# SP-3000PCB03.net
KiCad netlist of a schematic drawn in Altium Designer
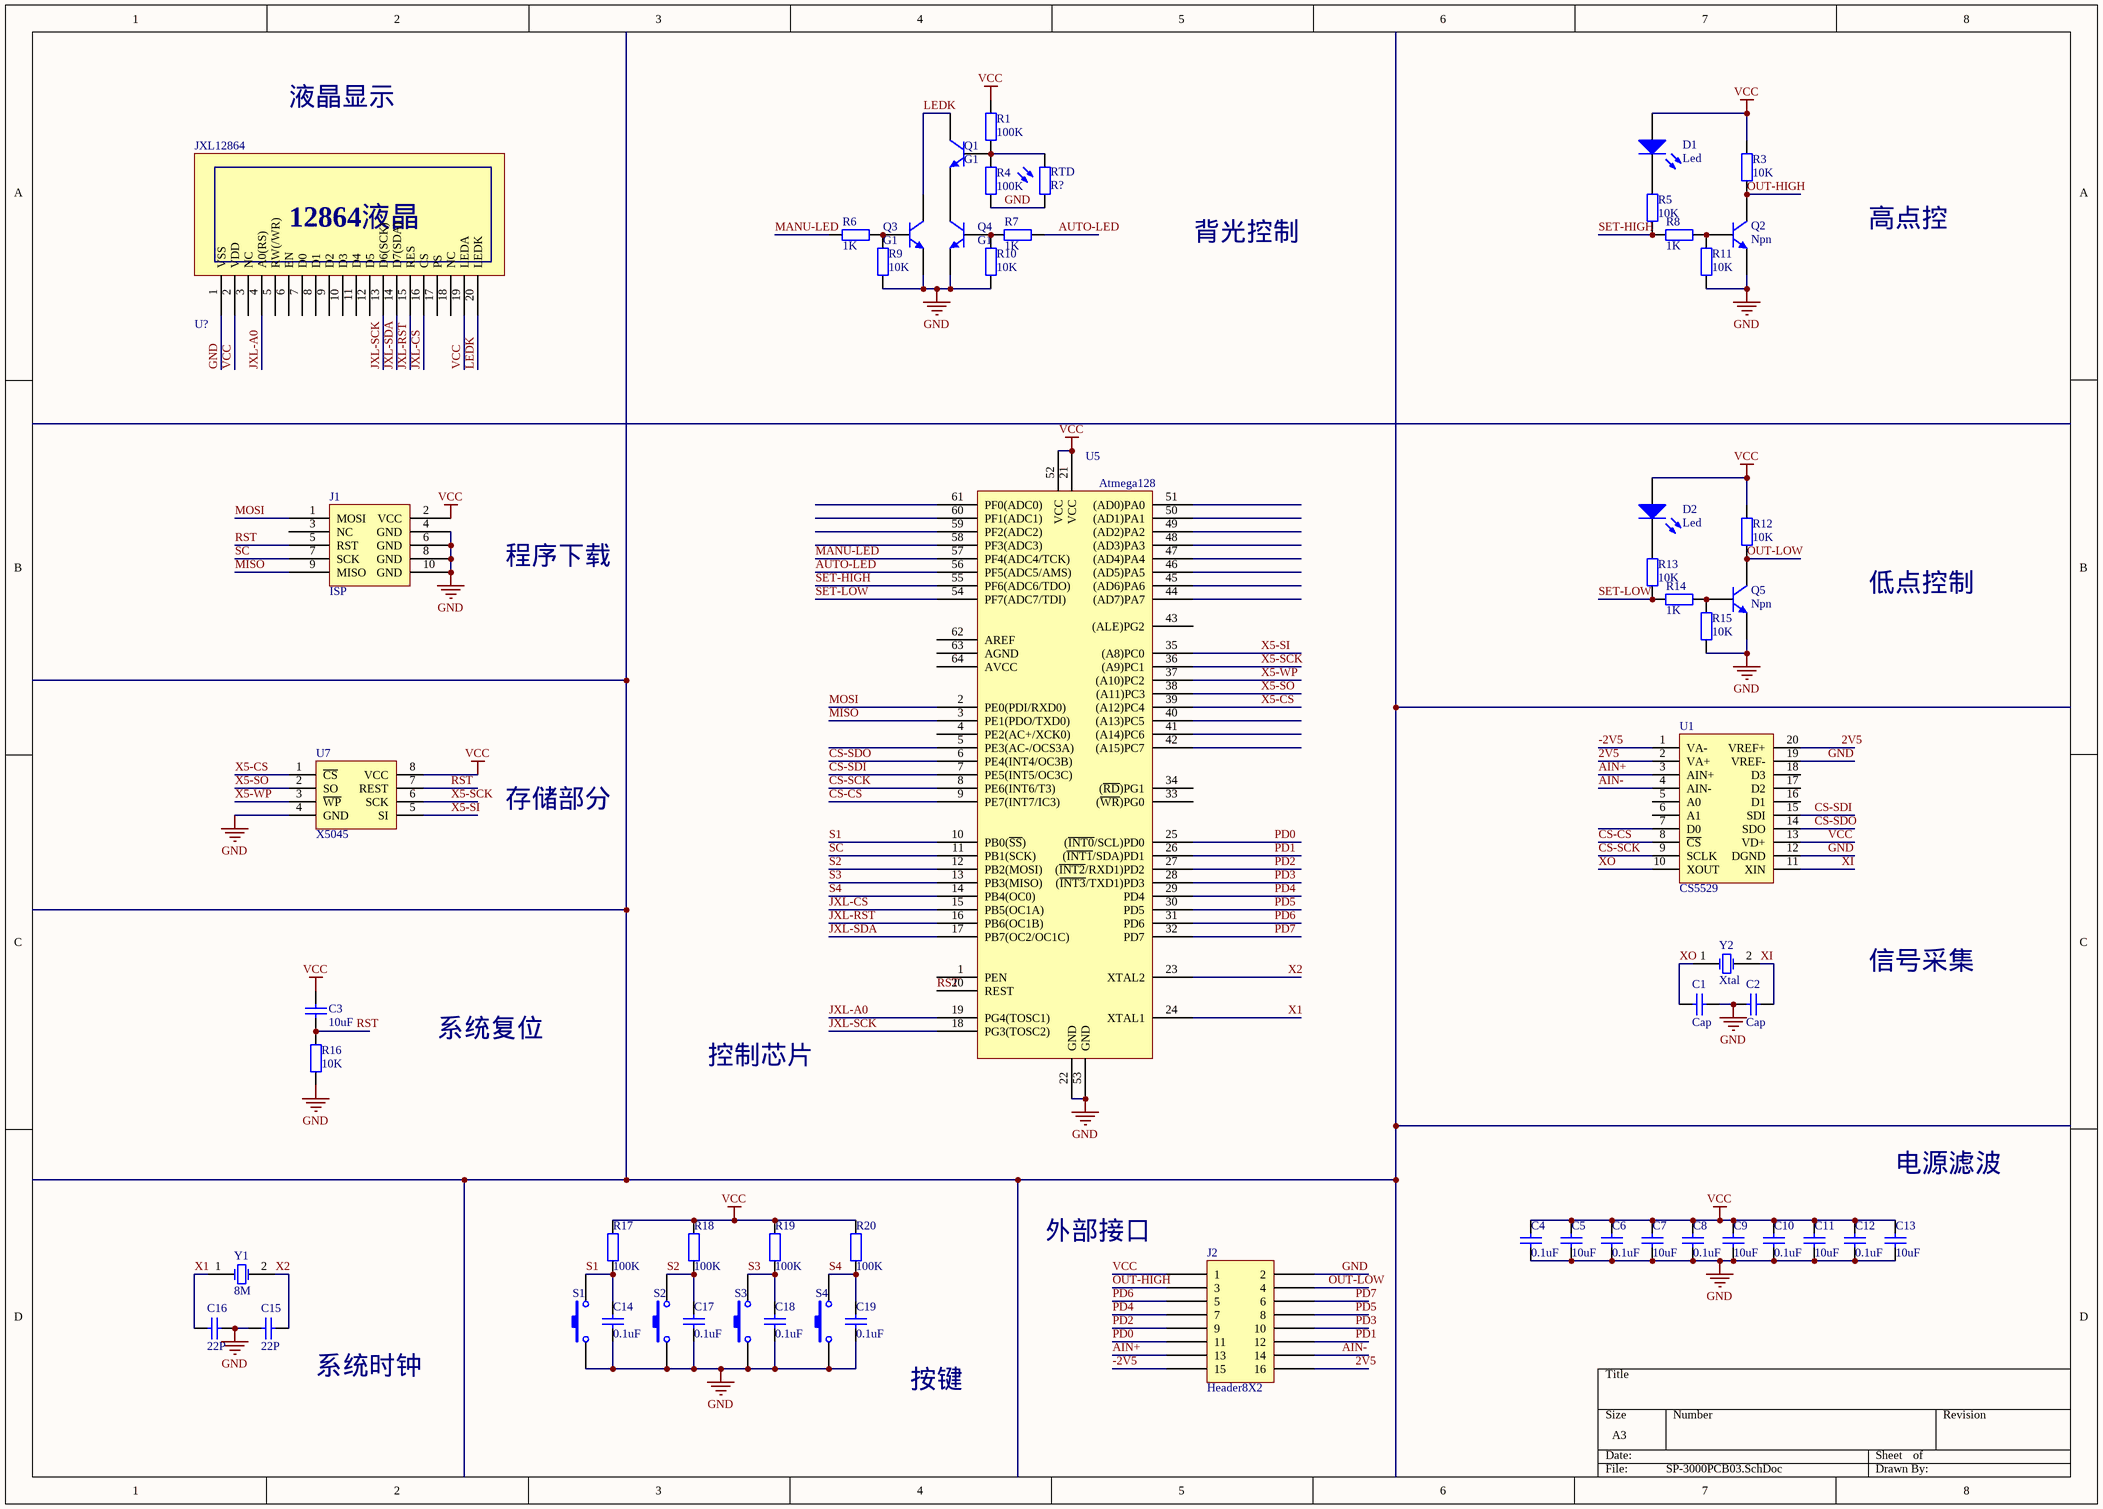
[diagram p0: SP-3000PCB03.SchDoc]

(export (version "E")
  (design (tool "Eeschema 10.0.6"))
  (components
    (comp (ref "C1") (value "Cap") (footprint "0805") (description "C?") (libsource (lib "常用库") (part "Cap")))
    (comp (ref "C2") (value "Cap") (footprint "0805") (description "C?") (libsource (lib "常用库") (part "Cap")))
    (comp (ref "C3")
      (value "10uF")
      (footprint "0805")
      (description "C?")
      (libsource (lib "常用库") (part "Cap"))
    )
    (comp (ref "C4")
      (value "0.1uF")
      (footprint "0805")
      (description "C?")
      (libsource (lib "常用库") (part "Cap"))
    )
    (comp (ref "C5")
      (value "10uF")
      (footprint "0805")
      (description "C?")
      (libsource (lib "常用库") (part "Cap"))
    )
    (comp (ref "C6")
      (value "0.1uF")
      (footprint "0805")
      (description "C?")
      (libsource (lib "常用库") (part "Cap"))
    )
    (comp (ref "C7")
      (value "10uF")
      (footprint "0805")
      (description "C?")
      (libsource (lib "常用库") (part "Cap"))
    )
    (comp (ref "C8")
      (value "0.1uF")
      (footprint "0805")
      (description "C?")
      (libsource (lib "常用库") (part "Cap"))
    )
    (comp (ref "C9")
      (value "10uF")
      (footprint "0805")
      (description "C?")
      (libsource (lib "常用库") (part "Cap"))
    )
    (comp (ref "C10")
      (value "0.1uF")
      (footprint "0805")
      (description "C?")
      (libsource (lib "常用库") (part "Cap"))
    )
    (comp (ref "C11")
      (value "10uF")
      (footprint "0805")
      (description "C?")
      (libsource (lib "常用库") (part "Cap"))
    )
    (comp (ref "C12")
      (value "0.1uF")
      (footprint "0805")
      (description "C?")
      (libsource (lib "常用库") (part "Cap"))
    )
    (comp (ref "C13")
      (value "10uF")
      (footprint "0805")
      (description "C?")
      (libsource (lib "常用库") (part "Cap"))
    )
    (comp (ref "C14")
      (value "0.1uF")
      (footprint "0805")
      (description "C?")
      (libsource (lib "常用库") (part "Cap"))
    )
    (comp (ref "C15")
      (value "22P")
      (footprint "0805")
      (description "C?")
      (libsource (lib "常用库") (part "Cap"))
    )
    (comp (ref "C16")
      (value "22P")
      (footprint "0805")
      (description "C?")
      (libsource (lib "常用库") (part "Cap"))
    )
    (comp (ref "C17")
      (value "0.1uF")
      (footprint "0805")
      (description "C?")
      (libsource (lib "常用库") (part "Cap"))
    )
    (comp (ref "C18")
      (value "0.1uF")
      (footprint "0805")
      (description "C?")
      (libsource (lib "常用库") (part "Cap"))
    )
    (comp (ref "C19")
      (value "0.1uF")
      (footprint "0805")
      (description "C?")
      (libsource (lib "常用库") (part "Cap"))
    )
    (comp (ref "D1") (value "Led") (footprint "LED") (description "D?") (libsource (lib "常用库") (part "Led")))
    (comp (ref "D2") (value "Led") (footprint "LED") (description "D?") (libsource (lib "常用库") (part "Led")))
    (comp (ref "J1")
      (value "ISP")
      (footprint "IDC10")
      (description "U?")
      (libsource (lib "常用库") (part "isp"))
    )
    (comp (ref "J2")
      (value "Header8X2")
      (footprint "IDC16")
      (description "H?")
      (libsource (lib "常用库") (part "Header8X2"))
    )
    (comp (ref "JXL12864") (value "U?") (footprint "JLX12864") (libsource (lib "常用库") (part "JLX12864")))
    (comp (ref "Q1") (value "G1") (footprint "9013") (description "Q?") (libsource (lib "常用库") (part "Npn")))
    (comp (ref "Q2") (value "Npn") (footprint "9013") (description "Q?") (libsource (lib "常用库") (part "Npn")))
    (comp (ref "Q3") (value "G1") (footprint "9013") (description "Q?") (libsource (lib "常用库") (part "Npn")))
    (comp (ref "Q4") (value "G1") (footprint "9013") (description "Q?") (libsource (lib "常用库") (part "Npn")))
    (comp (ref "Q5") (value "Npn") (footprint "9013") (description "Q?") (libsource (lib "常用库") (part "Npn")))
    (comp (ref "R1") (value "100K") (footprint "0805") (description "R?") (libsource (lib "") (part "Res_1")))
    (comp (ref "R3") (value "10K") (footprint "0805") (description "R?") (libsource (lib "常用库") (part "Res")))
    (comp (ref "R4") (value "100K") (footprint "0805") (description "R?") (libsource (lib "") (part "Res_1")))
    (comp (ref "R5") (value "10K") (footprint "0805") (description "R?") (libsource (lib "常用库") (part "Res")))
    (comp (ref "R6") (value "1K") (footprint "0805") (description "R?") (libsource (lib "") (part "Res_3")))
    (comp (ref "R7") (value "1K") (footprint "0805") (description "R?") (libsource (lib "") (part "Res_3")))
    (comp (ref "R8") (value "1K") (footprint "0805") (description "R?") (libsource (lib "") (part "Res_2")))
    (comp (ref "R9") (value "10K") (footprint "0805") (description "R?") (libsource (lib "常用库") (part "Res")))
    (comp (ref "R10")
      (value "10K")
      (footprint "0805")
      (description "R?")
      (libsource (lib "常用库") (part "Res"))
    )
    (comp (ref "R11")
      (value "10K")
      (footprint "0805")
      (description "R?")
      (libsource (lib "常用库") (part "Res"))
    )
    (comp (ref "R12")
      (value "10K")
      (footprint "0805")
      (description "R?")
      (libsource (lib "常用库") (part "Res"))
    )
    (comp (ref "R13")
      (value "10K")
      (footprint "0805")
      (description "R?")
      (libsource (lib "常用库") (part "Res"))
    )
    (comp (ref "R14") (value "1K") (footprint "0805") (description "R?") (libsource (lib "") (part "Res_2")))
    (comp (ref "R15")
      (value "10K")
      (footprint "0805")
      (description "R?")
      (libsource (lib "常用库") (part "Res"))
    )
    (comp (ref "R16")
      (value "10K")
      (footprint "0805")
      (description "R?")
      (libsource (lib "常用库") (part "Res"))
    )
    (comp (ref "R17")
      (value "100K")
      (footprint "0805")
      (description "R?")
      (libsource (lib "常用库") (part "Res"))
    )
    (comp (ref "R18")
      (value "100K")
      (footprint "0805")
      (description "R?")
      (libsource (lib "常用库") (part "Res"))
    )
    (comp (ref "R19")
      (value "100K")
      (footprint "0805")
      (description "R?")
      (libsource (lib "常用库") (part "Res"))
    )
    (comp (ref "R20")
      (value "100K")
      (footprint "0805")
      (description "R?")
      (libsource (lib "常用库") (part "Res"))
    )
    (comp (ref "RTD") (value "R?") (footprint "RTD") (libsource (lib "常用库") (part "光敏电阻")))
    (comp (ref "S1") (value "~") (footprint "SW") (description "S?") (libsource (lib "常用库") (part "Sw-pb")))
    (comp (ref "S2") (value "~") (footprint "SW") (description "S?") (libsource (lib "常用库") (part "Sw-pb")))
    (comp (ref "S3") (value "~") (footprint "SW") (description "S?") (libsource (lib "常用库") (part "Sw-pb")))
    (comp (ref "S4") (value "~") (footprint "SW") (description "S?") (libsource (lib "常用库") (part "Sw-pb")))
    (comp (ref "U1") (value "CS5529") (footprint "CS5529") (libsource (lib "常用库") (part "CS5529")))
    (comp (ref "U5")
      (value "Atmega128")
      (footprint "Quad64")
      (description "U?")
      (libsource (lib "常用库") (part "Atmega128"))
    )
    (comp (ref "U7") (value "X5045") (footprint "SOP8") (libsource (lib "常用库") (part "X5045")))
    (comp (ref "Y1") (value "8M") (footprint "CY") (description "Y?") (libsource (lib "常用库") (part "Xtal")))
    (comp (ref "Y2")
      (value "Xtal")
      (footprint "DIP2(32.768M)")
      (description "Y?")
      (libsource (lib "常用库") (part "Xtal"))
    )
  )
  (nets
    (net (code "1") (name "/-2V5") (class "Default")
      (node (ref "J2") (pin "15") (pinfunction "15_15") (pintype "passive"))
      (node (ref "U1") (pin "1") (pinfunction "VA-_1") (pintype "passive"))
    )
    (net (code "2") (name "/2V5") (class "Default")
      (node (ref "J2") (pin "16") (pinfunction "16_16") (pintype "passive"))
      (node (ref "U1") (pin "2") (pinfunction "VA+_2") (pintype "passive"))
      (node (ref "U1") (pin "20") (pinfunction "VREF+_20") (pintype "passive"))
    )
    (net (code "3") (name "/AIN+") (class "Default")
      (node (ref "J2") (pin "13") (pinfunction "13_13") (pintype "passive"))
      (node (ref "U1") (pin "3") (pinfunction "AIN+_3") (pintype "passive"))
    )
    (net (code "4") (name "/AIN-") (class "Default")
      (node (ref "J2") (pin "14") (pinfunction "14_14") (pintype "passive"))
      (node (ref "U1") (pin "4") (pinfunction "AIN-_4") (pintype "passive"))
    )
    (net (code "5") (name "/AUTO-LED") (class "Default")
      (node (ref "R7") (pin "1") (pinfunction "1_1") (pintype "passive"))
      (node (ref "U5") (pin "56") (pinfunction "PF5(ADC5/AMS)_56") (pintype "passive"))
    )
    (net (code "6") (name "/CS-CS") (class "Default")
      (node (ref "U1") (pin "8") (pinfunction "~{CS}_8") (pintype "passive"))
      (node (ref "U5") (pin "9") (pinfunction "PE7(INT7/IC3)_9") (pintype "passive"))
    )
    (net (code "7") (name "/CS-SCK") (class "Default")
      (node (ref "U1") (pin "9") (pinfunction "SCLK_9") (pintype "passive"))
      (node (ref "U5") (pin "8") (pinfunction "PE6(INT6/T3)_8") (pintype "passive"))
    )
    (net (code "8") (name "/CS-SDI") (class "Default")
      (node (ref "U1") (pin "15") (pinfunction "SDI_15") (pintype "passive"))
      (node (ref "U5") (pin "7") (pinfunction "PE5(INT5/OC3C)_7") (pintype "passive"))
    )
    (net (code "9") (name "/CS-SDO") (class "Default")
      (node (ref "U1") (pin "14") (pinfunction "SDO_14") (pintype "passive"))
      (node (ref "U5") (pin "6") (pinfunction "PE4(INT4/OC3B)_6") (pintype "passive"))
    )
    (net (code "10") (name "/JXL-A0") (class "Default")
      (node (ref "JXL12864") (pin "4") (pinfunction "A0(RS)_4") (pintype "passive"))
      (node (ref "U5") (pin "19") (pinfunction "PG4(TOSC1)_19") (pintype "passive"))
    )
    (net (code "11") (name "/JXL-CS") (class "Default")
      (node (ref "JXL12864") (pin "16") (pinfunction "CS_16") (pintype "passive"))
      (node (ref "U5") (pin "15") (pinfunction "PB5(OC1A)_15") (pintype "passive"))
    )
    (net (code "12") (name "/JXL-RST") (class "Default")
      (node (ref "JXL12864") (pin "15") (pinfunction "RES_15") (pintype "passive"))
      (node (ref "U5") (pin "16") (pinfunction "PB6(OC1B)_16") (pintype "passive"))
    )
    (net (code "13") (name "/JXL-SCK") (class "Default")
      (node (ref "JXL12864") (pin "13") (pinfunction "D6(SCK)_13") (pintype "passive"))
      (node (ref "U5") (pin "18") (pinfunction "PG3(TOSC2)_18") (pintype "passive"))
    )
    (net (code "14") (name "/JXL-SDA") (class "Default")
      (node (ref "JXL12864") (pin "14") (pinfunction "D7(SDA)_14") (pintype "passive"))
      (node (ref "U5") (pin "17") (pinfunction "PB7(OC2/OC1C)_17") (pintype "passive"))
    )
    (net (code "15") (name "/LEDK") (class "Default")
      (node (ref "JXL12864") (pin "20") (pinfunction "LEDK_20") (pintype "passive"))
      (node (ref "Q1") (pin "3") (pinfunction "C_3") (pintype "passive"))
      (node (ref "Q3") (pin "3") (pinfunction "C_3") (pintype "passive"))
    )
    (net (code "16") (name "/MANU-LED") (class "Default")
      (node (ref "R6") (pin "2") (pinfunction "2_2") (pintype "passive"))
      (node (ref "U5") (pin "57") (pinfunction "PF4(ADC4/TCK)_57") (pintype "passive"))
    )
    (net (code "17") (name "/MISO") (class "Default")
      (node (ref "J1") (pin "9") (pinfunction "MISO_9") (pintype "passive"))
      (node (ref "U5") (pin "3") (pinfunction "PE1(PDO/TXD0)_3") (pintype "passive"))
    )
    (net (code "18") (name "/MOSI") (class "Default")
      (node (ref "J1") (pin "1") (pinfunction "MOSI_1") (pintype "passive"))
      (node (ref "U5") (pin "2") (pinfunction "PE0(PDI/RXD0)_2") (pintype "passive"))
    )
    (net (code "19") (name "/OUT-HIGH") (class "Default")
      (node (ref "J2") (pin "3") (pinfunction "3_3") (pintype "passive"))
      (node (ref "Q2") (pin "3") (pinfunction "C_3") (pintype "passive"))
      (node (ref "R3") (pin "1") (pinfunction "1_1") (pintype "passive"))
    )
    (net (code "20") (name "/OUT-LOW") (class "Default")
      (node (ref "J2") (pin "4") (pinfunction "4_4") (pintype "passive"))
      (node (ref "Q5") (pin "3") (pinfunction "C_3") (pintype "passive"))
      (node (ref "R12") (pin "1") (pinfunction "1_1") (pintype "passive"))
    )
    (net (code "21") (name "/PD0") (class "Default")
      (node (ref "J2") (pin "11") (pinfunction "11_11") (pintype "passive"))
      (node (ref "U5") (pin "25") (pinfunction "(~{INT0}/SCL)PD0_25") (pintype "passive"))
    )
    (net (code "22") (name "/PD1") (class "Default")
      (node (ref "J2") (pin "12") (pinfunction "12_12") (pintype "passive"))
      (node (ref "U5") (pin "26") (pinfunction "(~{INT1}/SDA)PD1_26") (pintype "passive"))
    )
    (net (code "23") (name "/PD2") (class "Default")
      (node (ref "J2") (pin "9") (pinfunction "9_9") (pintype "passive"))
      (node (ref "U5") (pin "27") (pinfunction "(~{INT2}/RXD1)PD2_27") (pintype "passive"))
    )
    (net (code "24") (name "/PD3") (class "Default")
      (node (ref "J2") (pin "10") (pinfunction "10_10") (pintype "passive"))
      (node (ref "U5") (pin "28") (pinfunction "(~{INT3}/TXD1)PD3_28") (pintype "passive"))
    )
    (net (code "25") (name "/PD4") (class "Default")
      (node (ref "J2") (pin "7") (pinfunction "7_7") (pintype "passive"))
      (node (ref "U5") (pin "29") (pinfunction "PD4_29") (pintype "passive"))
    )
    (net (code "26") (name "/PD5") (class "Default")
      (node (ref "J2") (pin "8") (pinfunction "8_8") (pintype "passive"))
      (node (ref "U5") (pin "30") (pinfunction "PD5_30") (pintype "passive"))
    )
    (net (code "27") (name "/PD6") (class "Default")
      (node (ref "J2") (pin "5") (pinfunction "5_5") (pintype "passive"))
      (node (ref "U5") (pin "31") (pinfunction "PD6_31") (pintype "passive"))
    )
    (net (code "28") (name "/PD7") (class "Default")
      (node (ref "J2") (pin "6") (pinfunction "6_6") (pintype "passive"))
      (node (ref "U5") (pin "32") (pinfunction "PD7_32") (pintype "passive"))
    )
    (net (code "29") (name "/RST") (class "Default")
      (node (ref "C3") (pin "1") (pinfunction "1_1") (pintype "passive"))
      (node (ref "J1") (pin "5") (pinfunction "RST_5") (pintype "passive"))
      (node (ref "R16") (pin "2") (pinfunction "2_2") (pintype "passive"))
      (node (ref "U5") (pin "20") (pinfunction "REST_20") (pintype "passive"))
      (node (ref "U7") (pin "7") (pinfunction "REST_7") (pintype "passive"))
    )
    (net (code "30") (name "/S1") (class "Default")
      (node (ref "C14") (pin "2") (pinfunction "2_2") (pintype "passive"))
      (node (ref "R17") (pin "1") (pinfunction "1_1") (pintype "passive"))
      (node (ref "S1") (pin "2") (pinfunction "2_2") (pintype "passive"))
      (node (ref "U5") (pin "10") (pinfunction "PB0(~{SS})_10") (pintype "passive"))
    )
    (net (code "31") (name "/S2") (class "Default")
      (node (ref "C17") (pin "2") (pinfunction "2_2") (pintype "passive"))
      (node (ref "R18") (pin "1") (pinfunction "1_1") (pintype "passive"))
      (node (ref "S2") (pin "2") (pinfunction "2_2") (pintype "passive"))
      (node (ref "U5") (pin "12") (pinfunction "PB2(MOSI)_12") (pintype "passive"))
    )
    (net (code "32") (name "/S3") (class "Default")
      (node (ref "C18") (pin "2") (pinfunction "2_2") (pintype "passive"))
      (node (ref "R19") (pin "1") (pinfunction "1_1") (pintype "passive"))
      (node (ref "S3") (pin "2") (pinfunction "2_2") (pintype "passive"))
      (node (ref "U5") (pin "13") (pinfunction "PB3(MISO)_13") (pintype "passive"))
    )
    (net (code "33") (name "/S4") (class "Default")
      (node (ref "C19") (pin "2") (pinfunction "2_2") (pintype "passive"))
      (node (ref "R20") (pin "1") (pinfunction "1_1") (pintype "passive"))
      (node (ref "S4") (pin "2") (pinfunction "2_2") (pintype "passive"))
      (node (ref "U5") (pin "14") (pinfunction "PB4(OC0)_14") (pintype "passive"))
    )
    (net (code "34") (name "/SC") (class "Default")
      (node (ref "J1") (pin "7") (pinfunction "SCK_7") (pintype "passive"))
      (node (ref "U5") (pin "11") (pinfunction "PB1(SCK)_11") (pintype "passive"))
    )
    (net (code "35") (name "/SET-HIGH") (class "Default")
      (node (ref "R5") (pin "1") (pinfunction "1_1") (pintype "passive"))
      (node (ref "R8") (pin "1") (pinfunction "1_1") (pintype "passive"))
      (node (ref "U5") (pin "55") (pinfunction "PF6(ADC6/TDO)_55") (pintype "passive"))
    )
    (net (code "36") (name "/SET-LOW") (class "Default")
      (node (ref "R13") (pin "1") (pinfunction "1_1") (pintype "passive"))
      (node (ref "R14") (pin "1") (pinfunction "1_1") (pintype "passive"))
      (node (ref "U5") (pin "54") (pinfunction "PF7(ADC7/TDI)_54") (pintype "passive"))
    )
    (net (code "37") (name "/X1") (class "Default")
      (node (ref "C16") (pin "1") (pinfunction "1_1") (pintype "passive"))
      (node (ref "U5") (pin "24") (pinfunction "XTAL1_24") (pintype "passive"))
      (node (ref "Y1") (pin "1") (pinfunction "OSC1_1") (pintype "passive"))
    )
    (net (code "38") (name "/X2") (class "Default")
      (node (ref "C15") (pin "2") (pinfunction "2_2") (pintype "passive"))
      (node (ref "U5") (pin "23") (pinfunction "XTAL2_23") (pintype "passive"))
      (node (ref "Y1") (pin "2") (pinfunction "OSC2_2") (pintype "passive"))
    )
    (net (code "39") (name "/X5-CS") (class "Default")
      (node (ref "U5") (pin "39") (pinfunction "(A12)PC4_39") (pintype "passive"))
      (node (ref "U7") (pin "1") (pinfunction "~{CS}_1") (pintype "passive"))
    )
    (net (code "40") (name "/X5-SCK") (class "Default")
      (node (ref "U5") (pin "36") (pinfunction "(A9)PC1_36") (pintype "passive"))
      (node (ref "U7") (pin "6") (pinfunction "SCK_6") (pintype "passive"))
    )
    (net (code "41") (name "/X5-SI") (class "Default")
      (node (ref "U5") (pin "35") (pinfunction "(A8)PC0_35") (pintype "passive"))
      (node (ref "U7") (pin "5") (pinfunction "SI_5") (pintype "passive"))
    )
    (net (code "42") (name "/X5-SO") (class "Default")
      (node (ref "U5") (pin "38") (pinfunction "(A11)PC3_38") (pintype "passive"))
      (node (ref "U7") (pin "2") (pinfunction "SO_2") (pintype "passive"))
    )
    (net (code "43") (name "/X5-WP") (class "Default")
      (node (ref "U5") (pin "37") (pinfunction "(A10)PC2_37") (pintype "passive"))
      (node (ref "U7") (pin "3") (pinfunction "~{WP}_3") (pintype "passive"))
    )
    (net (code "44") (name "/XI") (class "Default")
      (node (ref "C2") (pin "2") (pinfunction "2_2") (pintype "passive"))
      (node (ref "U1") (pin "11") (pinfunction "XIN_11") (pintype "passive"))
      (node (ref "Y2") (pin "2") (pinfunction "OSC2_2") (pintype "passive"))
    )
    (net (code "45") (name "/XO") (class "Default")
      (node (ref "C1") (pin "1") (pinfunction "1_1") (pintype "passive"))
      (node (ref "U1") (pin "10") (pinfunction "XOUT_10") (pintype "passive"))
      (node (ref "Y2") (pin "1") (pinfunction "OSC1_1") (pintype "passive"))
    )
    (net (code "46") (name "GND") (class "Default")
      (node (ref "C1") (pin "2") (pinfunction "2_2") (pintype "passive"))
      (node (ref "C10") (pin "1") (pinfunction "1_1") (pintype "passive"))
      (node (ref "C11") (pin "1") (pinfunction "1_1") (pintype "passive"))
      (node (ref "C12") (pin "1") (pinfunction "1_1") (pintype "passive"))
      (node (ref "C13") (pin "1") (pinfunction "1_1") (pintype "passive"))
      (node (ref "C14") (pin "1") (pinfunction "1_1") (pintype "passive"))
      (node (ref "C15") (pin "1") (pinfunction "1_1") (pintype "passive"))
      (node (ref "C16") (pin "2") (pinfunction "2_2") (pintype "passive"))
      (node (ref "C17") (pin "1") (pinfunction "1_1") (pintype "passive"))
      (node (ref "C18") (pin "1") (pinfunction "1_1") (pintype "passive"))
      (node (ref "C19") (pin "1") (pinfunction "1_1") (pintype "passive"))
      (node (ref "C2") (pin "1") (pinfunction "1_1") (pintype "passive"))
      (node (ref "C4") (pin "1") (pinfunction "1_1") (pintype "passive"))
      (node (ref "C5") (pin "1") (pinfunction "1_1") (pintype "passive"))
      (node (ref "C6") (pin "1") (pinfunction "1_1") (pintype "passive"))
      (node (ref "C7") (pin "1") (pinfunction "1_1") (pintype "passive"))
      (node (ref "C8") (pin "1") (pinfunction "1_1") (pintype "passive"))
      (node (ref "C9") (pin "1") (pinfunction "1_1") (pintype "passive"))
      (node (ref "J1") (pin "10") (pinfunction "GND_10") (pintype "passive"))
      (node (ref "J1") (pin "4") (pinfunction "GND_4") (pintype "passive"))
      (node (ref "J1") (pin "6") (pinfunction "GND_6") (pintype "passive"))
      (node (ref "J1") (pin "8") (pinfunction "GND_8") (pintype "passive"))
      (node (ref "J2") (pin "2") (pinfunction "2_2") (pintype "passive"))
      (node (ref "JXL12864") (pin "1") (pinfunction "VSS_1") (pintype "passive"))
      (node (ref "Q2") (pin "2") (pinfunction "E_2") (pintype "passive"))
      (node (ref "Q3") (pin "2") (pinfunction "E_2") (pintype "passive"))
      (node (ref "Q4") (pin "2") (pinfunction "E_2") (pintype "passive"))
      (node (ref "Q5") (pin "2") (pinfunction "E_2") (pintype "passive"))
      (node (ref "R10") (pin "1") (pinfunction "1_1") (pintype "passive"))
      (node (ref "R11") (pin "1") (pinfunction "1_1") (pintype "passive"))
      (node (ref "R15") (pin "1") (pinfunction "1_1") (pintype "passive"))
      (node (ref "R16") (pin "1") (pinfunction "1_1") (pintype "passive"))
      (node (ref "R4") (pin "2") (pinfunction "2_2") (pintype "passive"))
      (node (ref "R9") (pin "1") (pinfunction "1_1") (pintype "passive"))
      (node (ref "RTD") (pin "1") (pinfunction "1_1") (pintype "passive"))
      (node (ref "S1") (pin "1") (pinfunction "1_1") (pintype "passive"))
      (node (ref "S2") (pin "1") (pinfunction "1_1") (pintype "passive"))
      (node (ref "S3") (pin "1") (pinfunction "1_1") (pintype "passive"))
      (node (ref "S4") (pin "1") (pinfunction "1_1") (pintype "passive"))
      (node (ref "U1") (pin "12") (pinfunction "DGND_12") (pintype "passive"))
      (node (ref "U1") (pin "19") (pinfunction "VREF-_19") (pintype "passive"))
      (node (ref "U5") (pin "22") (pinfunction "GND_22") (pintype "passive"))
      (node (ref "U5") (pin "53") (pinfunction "GND_53") (pintype "passive"))
      (node (ref "U7") (pin "4") (pinfunction "GND_4") (pintype "passive"))
    )
    (net (code "47") (name "Net-(D1-K)") (class "Default")
      (node (ref "D1") (pin "2") (pinfunction "K_2") (pintype "passive"))
      (node (ref "R5") (pin "2") (pinfunction "2_2") (pintype "passive"))
    )
    (net (code "48") (name "Net-(D2-K)") (class "Default")
      (node (ref "D2") (pin "2") (pinfunction "K_2") (pintype "passive"))
      (node (ref "R13") (pin "2") (pinfunction "2_2") (pintype "passive"))
    )
    (net (code "49") (name "Net-(Q1-B)") (class "Default")
      (node (ref "Q1") (pin "1") (pinfunction "B_1") (pintype "passive"))
      (node (ref "R1") (pin "2") (pinfunction "2_2") (pintype "passive"))
      (node (ref "R4") (pin "1") (pinfunction "1_1") (pintype "passive"))
      (node (ref "RTD") (pin "2") (pinfunction "2_2") (pintype "passive"))
    )
    (net (code "50") (name "Net-(Q1-E)") (class "Default")
      (node (ref "Q1") (pin "2") (pinfunction "E_2") (pintype "passive"))
      (node (ref "Q4") (pin "3") (pinfunction "C_3") (pintype "passive"))
    )
    (net (code "51") (name "Net-(Q2-B)") (class "Default")
      (node (ref "Q2") (pin "1") (pinfunction "B_1") (pintype "passive"))
      (node (ref "R11") (pin "2") (pinfunction "2_2") (pintype "passive"))
      (node (ref "R8") (pin "2") (pinfunction "2_2") (pintype "passive"))
    )
    (net (code "52") (name "Net-(Q3-B)") (class "Default")
      (node (ref "Q3") (pin "1") (pinfunction "B_1") (pintype "passive"))
      (node (ref "R6") (pin "1") (pinfunction "1_1") (pintype "passive"))
      (node (ref "R9") (pin "2") (pinfunction "2_2") (pintype "passive"))
    )
    (net (code "53") (name "Net-(Q4-B)") (class "Default")
      (node (ref "Q4") (pin "1") (pinfunction "B_1") (pintype "passive"))
      (node (ref "R10") (pin "2") (pinfunction "2_2") (pintype "passive"))
      (node (ref "R7") (pin "2") (pinfunction "2_2") (pintype "passive"))
    )
    (net (code "54") (name "Net-(Q5-B)") (class "Default")
      (node (ref "Q5") (pin "1") (pinfunction "B_1") (pintype "passive"))
      (node (ref "R14") (pin "2") (pinfunction "2_2") (pintype "passive"))
      (node (ref "R15") (pin "2") (pinfunction "2_2") (pintype "passive"))
    )
    (net (code "55") (name "VCC") (class "Default")
      (node (ref "C10") (pin "2") (pinfunction "2_2") (pintype "passive"))
      (node (ref "C11") (pin "2") (pinfunction "2_2") (pintype "passive"))
      (node (ref "C12") (pin "2") (pinfunction "2_2") (pintype "passive"))
      (node (ref "C13") (pin "2") (pinfunction "2_2") (pintype "passive"))
      (node (ref "C3") (pin "2") (pinfunction "2_2") (pintype "passive"))
      (node (ref "C4") (pin "2") (pinfunction "2_2") (pintype "passive"))
      (node (ref "C5") (pin "2") (pinfunction "2_2") (pintype "passive"))
      (node (ref "C6") (pin "2") (pinfunction "2_2") (pintype "passive"))
      (node (ref "C7") (pin "2") (pinfunction "2_2") (pintype "passive"))
      (node (ref "C8") (pin "2") (pinfunction "2_2") (pintype "passive"))
      (node (ref "C9") (pin "2") (pinfunction "2_2") (pintype "passive"))
      (node (ref "D1") (pin "1") (pinfunction "A_1") (pintype "passive"))
      (node (ref "D2") (pin "1") (pinfunction "A_1") (pintype "passive"))
      (node (ref "J1") (pin "2") (pinfunction "VCC_2") (pintype "passive"))
      (node (ref "J2") (pin "1") (pinfunction "1_1") (pintype "passive"))
      (node (ref "JXL12864") (pin "19") (pinfunction "LEDA_19") (pintype "passive"))
      (node (ref "JXL12864") (pin "2") (pinfunction "VDD_2") (pintype "passive"))
      (node (ref "R1") (pin "1") (pinfunction "1_1") (pintype "passive"))
      (node (ref "R12") (pin "2") (pinfunction "2_2") (pintype "passive"))
      (node (ref "R17") (pin "2") (pinfunction "2_2") (pintype "passive"))
      (node (ref "R18") (pin "2") (pinfunction "2_2") (pintype "passive"))
      (node (ref "R19") (pin "2") (pinfunction "2_2") (pintype "passive"))
      (node (ref "R20") (pin "2") (pinfunction "2_2") (pintype "passive"))
      (node (ref "R3") (pin "2") (pinfunction "2_2") (pintype "passive"))
      (node (ref "U1") (pin "13") (pinfunction "VD+_13") (pintype "passive"))
      (node (ref "U5") (pin "21") (pinfunction "VCC_21") (pintype "passive"))
      (node (ref "U5") (pin "52") (pinfunction "VCC_52") (pintype "passive"))
      (node (ref "U7") (pin "8") (pinfunction "VCC_8") (pintype "passive"))
    )
    (net (code "56") (name "unconnected-(J1-NC-Pad3)") (class "Default")
      (node (ref "J1") (pin "3") (pinfunction "NC_3") (pintype "passive"))
    )
    (net (code "57") (name "unconnected-(JXL12864-D0-Pad7)") (class "Default")
      (node (ref "JXL12864") (pin "7") (pinfunction "D0_7") (pintype "passive"))
    )
    (net (code "58") (name "unconnected-(JXL12864-D1-Pad8)") (class "Default")
      (node (ref "JXL12864") (pin "8") (pinfunction "D1_8") (pintype "passive"))
    )
    (net (code "59") (name "unconnected-(JXL12864-D2-Pad9)") (class "Default")
      (node (ref "JXL12864") (pin "9") (pinfunction "D2_9") (pintype "passive"))
    )
    (net (code "60") (name "unconnected-(JXL12864-D3-Pad10)") (class "Default")
      (node (ref "JXL12864") (pin "10") (pinfunction "D3_10") (pintype "passive"))
    )
    (net (code "61") (name "unconnected-(JXL12864-D4-Pad11)") (class "Default")
      (node (ref "JXL12864") (pin "11") (pinfunction "D4_11") (pintype "passive"))
    )
    (net (code "62") (name "unconnected-(JXL12864-D5-Pad12)") (class "Default")
      (node (ref "JXL12864") (pin "12") (pinfunction "D5_12") (pintype "passive"))
    )
    (net (code "63") (name "unconnected-(JXL12864-EN-Pad6)") (class "Default")
      (node (ref "JXL12864") (pin "6") (pinfunction "EN_6") (pintype "passive"))
    )
    (net (code "64") (name "unconnected-(JXL12864-NC-Pad3)") (class "Default")
      (node (ref "JXL12864") (pin "3") (pinfunction "NC_3") (pintype "passive"))
    )
    (net (code "65") (name "unconnected-(JXL12864-NC-Pad18)") (class "Default")
      (node (ref "JXL12864") (pin "18") (pinfunction "NC_18") (pintype "passive"))
    )
    (net (code "66") (name "unconnected-(JXL12864-PS-Pad17)") (class "Default")
      (node (ref "JXL12864") (pin "17") (pinfunction "PS_17") (pintype "passive"))
    )
    (net (code "67") (name "unconnected-(JXL12864-RW({slash}WR)-Pad5)") (class "Default")
      (node (ref "JXL12864") (pin "5") (pinfunction "RW(/WR)_5") (pintype "passive"))
    )
    (net (code "68") (name "unconnected-(U1-A0-Pad5)") (class "Default")
      (node (ref "U1") (pin "5") (pinfunction "A0_5") (pintype "passive"))
    )
    (net (code "69") (name "unconnected-(U1-A1-Pad6)") (class "Default")
      (node (ref "U1") (pin "6") (pinfunction "A1_6") (pintype "passive"))
    )
    (net (code "70") (name "unconnected-(U1-D0-Pad7)") (class "Default")
      (node (ref "U1") (pin "7") (pinfunction "D0_7") (pintype "passive"))
    )
    (net (code "71") (name "unconnected-(U1-D1-Pad16)") (class "Default")
      (node (ref "U1") (pin "16") (pinfunction "D1_16") (pintype "passive"))
    )
    (net (code "72") (name "unconnected-(U1-D2-Pad17)") (class "Default")
      (node (ref "U1") (pin "17") (pinfunction "D2_17") (pintype "passive"))
    )
    (net (code "73") (name "unconnected-(U1-D3-Pad18)") (class "Default")
      (node (ref "U1") (pin "18") (pinfunction "D3_18") (pintype "passive"))
    )
    (net (code "74") (name "unconnected-(U5-(A13)PC5-Pad40)") (class "Default")
      (node (ref "U5") (pin "40") (pinfunction "(A13)PC5_40") (pintype "passive"))
    )
    (net (code "75") (name "unconnected-(U5-(A14)PC6-Pad41)") (class "Default")
      (node (ref "U5") (pin "41") (pinfunction "(A14)PC6_41") (pintype "passive"))
    )
    (net (code "76") (name "unconnected-(U5-(A15)PC7-Pad42)") (class "Default")
      (node (ref "U5") (pin "42") (pinfunction "(A15)PC7_42") (pintype "passive"))
    )
    (net (code "77") (name "unconnected-(U5-(AD0)PA0-Pad51)") (class "Default")
      (node (ref "U5") (pin "51") (pinfunction "(AD0)PA0_51") (pintype "passive"))
    )
    (net (code "78") (name "unconnected-(U5-(AD1)PA1-Pad50)") (class "Default")
      (node (ref "U5") (pin "50") (pinfunction "(AD1)PA1_50") (pintype "passive"))
    )
    (net (code "79") (name "unconnected-(U5-(AD2)PA2-Pad49)") (class "Default")
      (node (ref "U5") (pin "49") (pinfunction "(AD2)PA2_49") (pintype "passive"))
    )
    (net (code "80") (name "unconnected-(U5-(AD3)PA3-Pad48)") (class "Default")
      (node (ref "U5") (pin "48") (pinfunction "(AD3)PA3_48") (pintype "passive"))
    )
    (net (code "81") (name "unconnected-(U5-(AD4)PA4-Pad47)") (class "Default")
      (node (ref "U5") (pin "47") (pinfunction "(AD4)PA4_47") (pintype "passive"))
    )
    (net (code "82") (name "unconnected-(U5-(AD5)PA5-Pad46)") (class "Default")
      (node (ref "U5") (pin "46") (pinfunction "(AD5)PA5_46") (pintype "passive"))
    )
    (net (code "83") (name "unconnected-(U5-(AD6)PA6-Pad45)") (class "Default")
      (node (ref "U5") (pin "45") (pinfunction "(AD6)PA6_45") (pintype "passive"))
    )
    (net (code "84") (name "unconnected-(U5-(AD7)PA7-Pad44)") (class "Default")
      (node (ref "U5") (pin "44") (pinfunction "(AD7)PA7_44") (pintype "passive"))
    )
    (net (code "85") (name "unconnected-(U5-(ALE)PG2-Pad43)") (class "Default")
      (node (ref "U5") (pin "43") (pinfunction "(ALE)PG2_43") (pintype "passive"))
    )
    (net (code "86") (name "unconnected-(U5-(~{RD})PG1-Pad34)") (class "Default")
      (node (ref "U5") (pin "34") (pinfunction "(~{RD})PG1_34") (pintype "passive"))
    )
    (net (code "87") (name "unconnected-(U5-(~{WR})PG0-Pad33)") (class "Default")
      (node (ref "U5") (pin "33") (pinfunction "(~{WR})PG0_33") (pintype "passive"))
    )
    (net (code "88") (name "unconnected-(U5-AGND-Pad63)") (class "Default")
      (node (ref "U5") (pin "63") (pinfunction "AGND_63") (pintype "passive"))
    )
    (net (code "89") (name "unconnected-(U5-AREF-Pad62)") (class "Default")
      (node (ref "U5") (pin "62") (pinfunction "AREF_62") (pintype "passive"))
    )
    (net (code "90") (name "unconnected-(U5-AVCC-Pad64)") (class "Default")
      (node (ref "U5") (pin "64") (pinfunction "AVCC_64") (pintype "passive"))
    )
    (net (code "91") (name "unconnected-(U5-PE2(AC+{slash}XCK0)-Pad4)") (class "Default")
      (node (ref "U5") (pin "4") (pinfunction "PE2(AC+/XCK0)_4") (pintype "passive"))
    )
    (net (code "92") (name "unconnected-(U5-PE3(AC-{slash}OCS3A)-Pad5)") (class "Default")
      (node (ref "U5") (pin "5") (pinfunction "PE3(AC-/OCS3A)_5") (pintype "passive"))
    )
    (net (code "93") (name "unconnected-(U5-PEN-Pad1)") (class "Default")
      (node (ref "U5") (pin "1") (pinfunction "PEN_1") (pintype "passive"))
    )
    (net (code "94") (name "unconnected-(U5-PF0(ADC0)-Pad61)") (class "Default")
      (node (ref "U5") (pin "61") (pinfunction "PF0(ADC0)_61") (pintype "passive"))
    )
    (net (code "95") (name "unconnected-(U5-PF1(ADC1)-Pad60)") (class "Default")
      (node (ref "U5") (pin "60") (pinfunction "PF1(ADC1)_60") (pintype "passive"))
    )
    (net (code "96") (name "unconnected-(U5-PF2(ADC2)-Pad59)") (class "Default")
      (node (ref "U5") (pin "59") (pinfunction "PF2(ADC2)_59") (pintype "passive"))
    )
    (net (code "97") (name "unconnected-(U5-PF3(ADC3)-Pad58)") (class "Default")
      (node (ref "U5") (pin "58") (pinfunction "PF3(ADC3)_58") (pintype "passive"))
    )
  )
)
